# USB7206C.net
KiCad netlist of a schematic drawn in Altium Designer
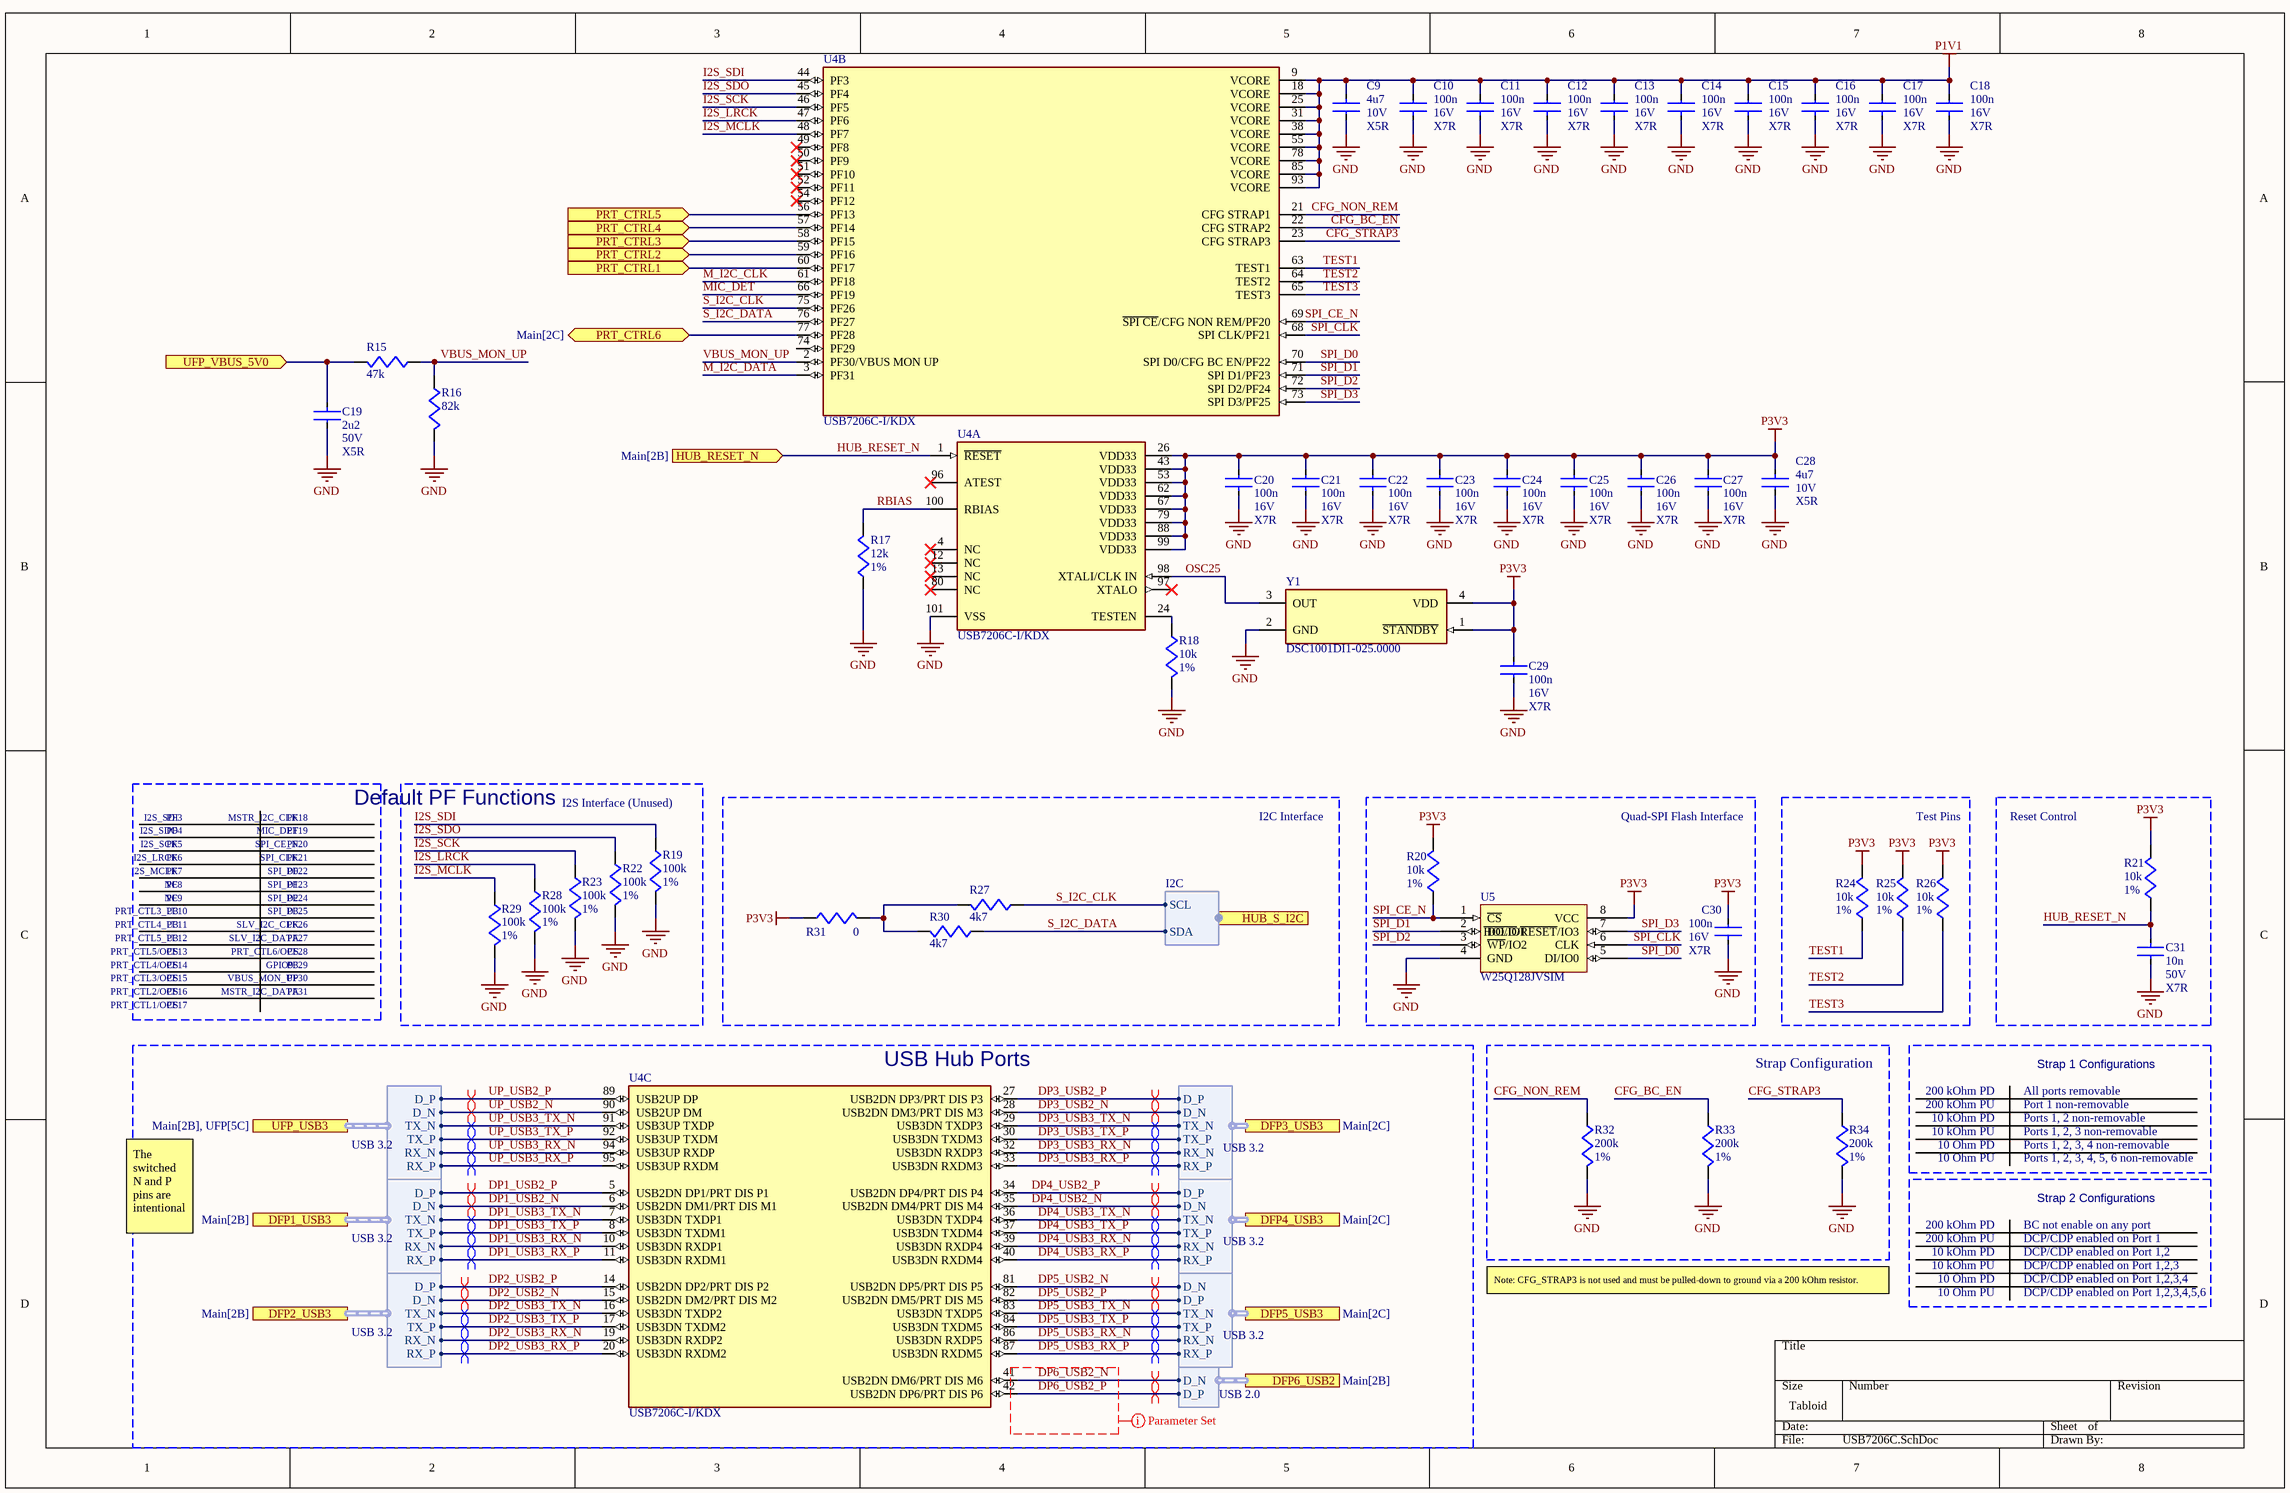
[diagram p0: USB7206C.SchDoc]

(export (version "E")
  (design (tool "Eeschema 10.0.6"))
  (components
    (comp (ref "C9")
      (value "4u7")
      (footprint "CAPC1005X06N")
      (description "10V 4.7uF X5R ±10% 0402 Multilayer Ceramic Capacitors MLCC - SMD/SMT ROHS")
      (fields
        (field (name "VOLTAGE") "10V")
        (field (name "DIELECTRIC") "X5R")
        (field (name "LCSC PART #") "C368809")
        (field (name "Comment") "4.7uF 10V 0402")
      )
      (libsource (lib "CWRU Motorsports") (part "Capacitor"))
    )
    (comp (ref "C10")
      (value "100n")
      (footprint "CAPC1005X06N")
      (description "16V 100nF X7R ±10% 0402 Multilayer Ceramic Capacitors MLCC - SMD/SMT ROHS")
      (fields
        (field (name "VOLTAGE") "16V")
        (field (name "DIELECTRIC") "X7R")
        (field (name "LCSC PART #") "C1525")
        (field (name "Comment") "100nF 16V 0402")
      )
      (libsource (lib "CWRU Motorsports") (part "Capacitor"))
    )
    (comp (ref "C11")
      (value "100n")
      (footprint "CAPC1005X06N")
      (description "16V 100nF X7R ±10% 0402 Multilayer Ceramic Capacitors MLCC - SMD/SMT ROHS")
      (fields
        (field (name "VOLTAGE") "16V")
        (field (name "DIELECTRIC") "X7R")
        (field (name "LCSC PART #") "C1525")
        (field (name "Comment") "100nF 16V 0402")
      )
      (libsource (lib "CWRU Motorsports") (part "Capacitor"))
    )
    (comp (ref "C12")
      (value "100n")
      (footprint "CAPC1005X06N")
      (description "16V 100nF X7R ±10% 0402 Multilayer Ceramic Capacitors MLCC - SMD/SMT ROHS")
      (fields
        (field (name "VOLTAGE") "16V")
        (field (name "DIELECTRIC") "X7R")
        (field (name "LCSC PART #") "C1525")
        (field (name "Comment") "100nF 16V 0402")
      )
      (libsource (lib "CWRU Motorsports") (part "Capacitor"))
    )
    (comp (ref "C13")
      (value "100n")
      (footprint "CAPC1005X06N")
      (description "16V 100nF X7R ±10% 0402 Multilayer Ceramic Capacitors MLCC - SMD/SMT ROHS")
      (fields
        (field (name "VOLTAGE") "16V")
        (field (name "DIELECTRIC") "X7R")
        (field (name "LCSC PART #") "C1525")
        (field (name "Comment") "100nF 16V 0402")
      )
      (libsource (lib "CWRU Motorsports") (part "Capacitor"))
    )
    (comp (ref "C14")
      (value "100n")
      (footprint "CAPC1005X06N")
      (description "16V 100nF X7R ±10% 0402 Multilayer Ceramic Capacitors MLCC - SMD/SMT ROHS")
      (fields
        (field (name "VOLTAGE") "16V")
        (field (name "DIELECTRIC") "X7R")
        (field (name "LCSC PART #") "C1525")
        (field (name "Comment") "100nF 16V 0402")
      )
      (libsource (lib "CWRU Motorsports") (part "Capacitor"))
    )
    (comp (ref "C15")
      (value "100n")
      (footprint "CAPC1005X06N")
      (description "16V 100nF X7R ±10% 0402 Multilayer Ceramic Capacitors MLCC - SMD/SMT ROHS")
      (fields
        (field (name "VOLTAGE") "16V")
        (field (name "DIELECTRIC") "X7R")
        (field (name "LCSC PART #") "C1525")
        (field (name "Comment") "100nF 16V 0402")
      )
      (libsource (lib "CWRU Motorsports") (part "Capacitor"))
    )
    (comp (ref "C16")
      (value "100n")
      (footprint "CAPC1005X06N")
      (description "16V 100nF X7R ±10% 0402 Multilayer Ceramic Capacitors MLCC - SMD/SMT ROHS")
      (fields
        (field (name "VOLTAGE") "16V")
        (field (name "DIELECTRIC") "X7R")
        (field (name "LCSC PART #") "C1525")
        (field (name "Comment") "100nF 16V 0402")
      )
      (libsource (lib "CWRU Motorsports") (part "Capacitor"))
    )
    (comp (ref "C17")
      (value "100n")
      (footprint "CAPC1005X06N")
      (description "16V 100nF X7R ±10% 0402 Multilayer Ceramic Capacitors MLCC - SMD/SMT ROHS")
      (fields
        (field (name "VOLTAGE") "16V")
        (field (name "DIELECTRIC") "X7R")
        (field (name "LCSC PART #") "C1525")
        (field (name "Comment") "100nF 16V 0402")
      )
      (libsource (lib "CWRU Motorsports") (part "Capacitor"))
    )
    (comp (ref "C18")
      (value "100n")
      (footprint "CAPC1005X06N")
      (description "16V 100nF X7R ±10% 0402 Multilayer Ceramic Capacitors MLCC - SMD/SMT ROHS")
      (fields
        (field (name "VOLTAGE") "16V")
        (field (name "DIELECTRIC") "X7R")
        (field (name "LCSC PART #") "C1525")
        (field (name "Comment") "100nF 16V 0402")
      )
      (libsource (lib "CWRU Motorsports") (part "Capacitor"))
    )
    (comp (ref "C19")
      (value "2u2")
      (footprint "CAPC2012X14N")
      (description "50V 2.2uF X5R ±10% 0805 Multilayer Ceramic Capacitors MLCC - SMD/SMT ROHS")
      (fields
        (field (name "VOLTAGE") "50V")
        (field (name "DIELECTRIC") "X5R")
        (field (name "LCSC PART #") "C377773")
        (field (name "Comment") "2.2uF 50V 0805")
      )
      (libsource (lib "CWRU Motorsports") (part "Capacitor"))
    )
    (comp (ref "C20")
      (value "100n")
      (footprint "CAPC1005X06N")
      (description "16V 100nF X7R ±10% 0402 Multilayer Ceramic Capacitors MLCC - SMD/SMT ROHS")
      (fields
        (field (name "VOLTAGE") "16V")
        (field (name "DIELECTRIC") "X7R")
        (field (name "LCSC PART #") "C1525")
        (field (name "Comment") "100nF 16V 0402")
      )
      (libsource (lib "CWRU Motorsports") (part "Capacitor"))
    )
    (comp (ref "C21")
      (value "100n")
      (footprint "CAPC1005X06N")
      (description "16V 100nF X7R ±10% 0402 Multilayer Ceramic Capacitors MLCC - SMD/SMT ROHS")
      (fields
        (field (name "VOLTAGE") "16V")
        (field (name "DIELECTRIC") "X7R")
        (field (name "LCSC PART #") "C1525")
        (field (name "Comment") "100nF 16V 0402")
      )
      (libsource (lib "CWRU Motorsports") (part "Capacitor"))
    )
    (comp (ref "C22")
      (value "100n")
      (footprint "CAPC1005X06N")
      (description "16V 100nF X7R ±10% 0402 Multilayer Ceramic Capacitors MLCC - SMD/SMT ROHS")
      (fields
        (field (name "VOLTAGE") "16V")
        (field (name "DIELECTRIC") "X7R")
        (field (name "LCSC PART #") "C1525")
        (field (name "Comment") "100nF 16V 0402")
      )
      (libsource (lib "CWRU Motorsports") (part "Capacitor"))
    )
    (comp (ref "C23")
      (value "100n")
      (footprint "CAPC1005X06N")
      (description "16V 100nF X7R ±10% 0402 Multilayer Ceramic Capacitors MLCC - SMD/SMT ROHS")
      (fields
        (field (name "VOLTAGE") "16V")
        (field (name "DIELECTRIC") "X7R")
        (field (name "LCSC PART #") "C1525")
        (field (name "Comment") "100nF 16V 0402")
      )
      (libsource (lib "CWRU Motorsports") (part "Capacitor"))
    )
    (comp (ref "C24")
      (value "100n")
      (footprint "CAPC1005X06N")
      (description "16V 100nF X7R ±10% 0402 Multilayer Ceramic Capacitors MLCC - SMD/SMT ROHS")
      (fields
        (field (name "VOLTAGE") "16V")
        (field (name "DIELECTRIC") "X7R")
        (field (name "LCSC PART #") "C1525")
        (field (name "Comment") "100nF 16V 0402")
      )
      (libsource (lib "CWRU Motorsports") (part "Capacitor"))
    )
    (comp (ref "C25")
      (value "100n")
      (footprint "CAPC1005X06N")
      (description "16V 100nF X7R ±10% 0402 Multilayer Ceramic Capacitors MLCC - SMD/SMT ROHS")
      (fields
        (field (name "VOLTAGE") "16V")
        (field (name "DIELECTRIC") "X7R")
        (field (name "LCSC PART #") "C1525")
        (field (name "Comment") "100nF 16V 0402")
      )
      (libsource (lib "CWRU Motorsports") (part "Capacitor"))
    )
    (comp (ref "C26")
      (value "100n")
      (footprint "CAPC1005X06N")
      (description "16V 100nF X7R ±10% 0402 Multilayer Ceramic Capacitors MLCC - SMD/SMT ROHS")
      (fields
        (field (name "VOLTAGE") "16V")
        (field (name "DIELECTRIC") "X7R")
        (field (name "LCSC PART #") "C1525")
        (field (name "Comment") "100nF 16V 0402")
      )
      (libsource (lib "CWRU Motorsports") (part "Capacitor"))
    )
    (comp (ref "C27")
      (value "100n")
      (footprint "CAPC1005X06N")
      (description "16V 100nF X7R ±10% 0402 Multilayer Ceramic Capacitors MLCC - SMD/SMT ROHS")
      (fields
        (field (name "VOLTAGE") "16V")
        (field (name "DIELECTRIC") "X7R")
        (field (name "LCSC PART #") "C1525")
        (field (name "Comment") "100nF 16V 0402")
      )
      (libsource (lib "CWRU Motorsports") (part "Capacitor"))
    )
    (comp (ref "C28")
      (value "4u7")
      (footprint "CAPC1005X06N")
      (description "10V 4.7uF X5R ±10% 0402 Multilayer Ceramic Capacitors MLCC - SMD/SMT ROHS")
      (fields
        (field (name "VOLTAGE") "10V")
        (field (name "DIELECTRIC") "X5R")
        (field (name "LCSC PART #") "C368809")
        (field (name "Comment") "4.7uF 10V 0402")
      )
      (libsource (lib "CWRU Motorsports") (part "Capacitor"))
    )
    (comp (ref "C29")
      (value "100n")
      (footprint "CAPC1005X06N")
      (description "16V 100nF X7R ±10% 0402 Multilayer Ceramic Capacitors MLCC - SMD/SMT ROHS")
      (fields
        (field (name "VOLTAGE") "16V")
        (field (name "DIELECTRIC") "X7R")
        (field (name "LCSC PART #") "C1525")
        (field (name "Comment") "100nF 16V 0402")
      )
      (libsource (lib "CWRU Motorsports") (part "Capacitor"))
    )
    (comp (ref "C30")
      (value "100n")
      (footprint "CAPC1005X06N")
      (description "16V 100nF X7R ±10% 0402 Multilayer Ceramic Capacitors MLCC - SMD/SMT ROHS")
      (fields
        (field (name "VOLTAGE") "16V")
        (field (name "DIELECTRIC") "X7R")
        (field (name "LCSC PART #") "C1525")
        (field (name "Comment") "100nF 16V 0402")
      )
      (libsource (lib "CWRU Motorsports") (part "Capacitor"))
    )
    (comp (ref "C31")
      (value "10n")
      (footprint "CAPC1005X06N")
      (description "50V 10nF X7R ±10% 0402 Multilayer Ceramic Capacitors MLCC - SMD/SMT ROHS")
      (fields
        (field (name "VOLTAGE") "50V")
        (field (name "DIELECTRIC") "X7R")
        (field (name "LCSC PART #") "C60133")
        (field (name "Comment") "10n 50V X7R 0402")
      )
      (libsource (lib "CWRU Motorsports") (part "Capacitor"))
    )
    (comp (ref "R15")
      (value "47k")
      (footprint "RESC1005X04M")
      (description "62.5mW Thick Film Resistors 50V ±100ppm/℃ ±5% 47kΩ 0402 Chip Resistor - Surface Mount ROHS")
      (fields (field (name "TOLERANCE") "1%") (field (name "LCSC PART #") "C163440"))
      (libsource (lib "CWRU Motorsports") (part "Resistor"))
    )
    (comp (ref "R16")
      (value "82k")
      (footprint "RESC1005X04M")
      (description "62.5mW Thick Film Resistors 50V ±100ppm/℃ ±1% 82kΩ 0402 Chip Resistor - Surface Mount ROHS")
      (fields (field (name "TOLERANCE") "1%") (field (name "LCSC PART #") "C137932"))
      (libsource (lib "CWRU Motorsports") (part "Resistor"))
    )
    (comp (ref "R17")
      (value "12k")
      (footprint "RESC1005X04M")
      (description "62.5mW Thick Film Resistors 50V ±100ppm/℃ ±1% 12kΩ 0402 Chip Resistor - Surface Mount ROHS")
      (fields
        (field (name "TOLERANCE") "1%")
        (field (name "LCSC PART #") "C114760")
        (field (name "Comment") "12k 1% 0402")
      )
      (libsource (lib "CWRU Motorsports") (part "Resistor"))
    )
    (comp (ref "R18")
      (value "10k")
      (footprint "RESC1005X04M")
      (description "62.5mW Thick Film Resistors 50V ±100ppm/℃ ±1% 10kΩ 0402 Chip Resistor - Surface Mount ROHS")
      (fields
        (field (name "TOLERANCE") "1%")
        (field (name "LCSC PART #") "C60490")
        (field (name "Comment") "10k 1% 0402")
      )
      (libsource (lib "CWRU Motorsports") (part "Resistor"))
    )
    (comp (ref "R19")
      (value "100k")
      (footprint "RESC1005X04M")
      (description "62.5mW Thick Film Resistors 50V ±100ppm/℃ ±1% 100kΩ 0402 Chip Resistor - Surface Mount ROHS")
      (fields
        (field (name "TOLERANCE") "1%")
        (field (name "LCSC PART #") "C60491")
        (field (name "Comment") "100k 1% 0402")
      )
      (libsource (lib "CWRU Motorsports") (part "Resistor"))
    )
    (comp (ref "R20")
      (value "10k")
      (footprint "RESC1005X04M")
      (description "62.5mW Thick Film Resistors 50V ±100ppm/℃ ±1% 10kΩ 0402 Chip Resistor - Surface Mount ROHS")
      (fields
        (field (name "TOLERANCE") "1%")
        (field (name "LCSC PART #") "C60490")
        (field (name "Comment") "10k 1% 0402")
      )
      (libsource (lib "CWRU Motorsports") (part "Resistor"))
    )
    (comp (ref "R21")
      (value "10k")
      (footprint "RESC1005X04M")
      (description "62.5mW Thick Film Resistors 50V ±100ppm/℃ ±1% 10kΩ 0402 Chip Resistor - Surface Mount ROHS")
      (fields
        (field (name "TOLERANCE") "1%")
        (field (name "LCSC PART #") "C60490")
        (field (name "Comment") "10k 1% 0402")
      )
      (libsource (lib "CWRU Motorsports") (part "Resistor"))
    )
    (comp (ref "R22")
      (value "100k")
      (footprint "RESC1005X04M")
      (description "62.5mW Thick Film Resistors 50V ±100ppm/℃ ±1% 100kΩ 0402 Chip Resistor - Surface Mount ROHS")
      (fields
        (field (name "TOLERANCE") "1%")
        (field (name "LCSC PART #") "C60491")
        (field (name "Comment") "100k 1% 0402")
      )
      (libsource (lib "CWRU Motorsports") (part "Resistor"))
    )
    (comp (ref "R23")
      (value "100k")
      (footprint "RESC1005X04M")
      (description "62.5mW Thick Film Resistors 50V ±100ppm/℃ ±1% 100kΩ 0402 Chip Resistor - Surface Mount ROHS")
      (fields
        (field (name "TOLERANCE") "1%")
        (field (name "LCSC PART #") "C60491")
        (field (name "Comment") "100k 1% 0402")
      )
      (libsource (lib "CWRU Motorsports") (part "Resistor"))
    )
    (comp (ref "R24")
      (value "10k")
      (footprint "RESC1005X04M")
      (description "62.5mW Thick Film Resistors 50V ±100ppm/℃ ±1% 10kΩ 0402 Chip Resistor - Surface Mount ROHS")
      (fields
        (field (name "TOLERANCE") "1%")
        (field (name "LCSC PART #") "C60490")
        (field (name "Comment") "10k 1% 0402")
      )
      (libsource (lib "CWRU Motorsports") (part "Resistor"))
    )
    (comp (ref "R25")
      (value "10k")
      (footprint "RESC1005X04M")
      (description "62.5mW Thick Film Resistors 50V ±100ppm/℃ ±1% 10kΩ 0402 Chip Resistor - Surface Mount ROHS")
      (fields
        (field (name "TOLERANCE") "1%")
        (field (name "LCSC PART #") "C60490")
        (field (name "Comment") "10k 1% 0402")
      )
      (libsource (lib "CWRU Motorsports") (part "Resistor"))
    )
    (comp (ref "R26")
      (value "10k")
      (footprint "RESC1005X04M")
      (description "62.5mW Thick Film Resistors 50V ±100ppm/℃ ±1% 10kΩ 0402 Chip Resistor - Surface Mount ROHS")
      (fields
        (field (name "TOLERANCE") "1%")
        (field (name "LCSC PART #") "C60490")
        (field (name "Comment") "10k 1% 0402")
      )
      (libsource (lib "CWRU Motorsports") (part "Resistor"))
    )
    (comp (ref "R27")
      (value "4k7")
      (footprint "RESC1005X04M")
      (description "62.5mW Thick Film Resistors 50V ±100ppm/℃ ±5% 4.7kΩ 0402 Chip Resistor - Surface Mount ROHS")
      (fields (field (name "TOLERANCE") "5%") (field (name "LCSC PART #") "C105870"))
      (libsource (lib "CWRU Motorsports") (part "Resistor"))
    )
    (comp (ref "R28")
      (value "100k")
      (footprint "RESC1005X04M")
      (description "62.5mW Thick Film Resistors 50V ±100ppm/℃ ±1% 100kΩ 0402 Chip Resistor - Surface Mount ROHS")
      (fields
        (field (name "TOLERANCE") "1%")
        (field (name "LCSC PART #") "C60491")
        (field (name "Comment") "100k 1% 0402")
      )
      (libsource (lib "CWRU Motorsports") (part "Resistor"))
    )
    (comp (ref "R29")
      (value "100k")
      (footprint "RESC1005X04M")
      (description "62.5mW Thick Film Resistors 50V ±100ppm/℃ ±1% 100kΩ 0402 Chip Resistor - Surface Mount ROHS")
      (fields
        (field (name "TOLERANCE") "1%")
        (field (name "LCSC PART #") "C60491")
        (field (name "Comment") "100k 1% 0402")
      )
      (libsource (lib "CWRU Motorsports") (part "Resistor"))
    )
    (comp (ref "R30")
      (value "4k7")
      (footprint "RESC1005X04M")
      (description "62.5mW Thick Film Resistors 50V ±100ppm/℃ ±5% 4.7kΩ 0402 Chip Resistor - Surface Mount ROHS")
      (fields (field (name "TOLERANCE") "5%") (field (name "LCSC PART #") "C105870"))
      (libsource (lib "CWRU Motorsports") (part "Resistor"))
    )
    (comp (ref "R31")
      (value "0")
      (footprint "RESC1508X05M")
      (description "62.5mW Thick Film Resistors 50V 0Ω 0402 Chip Resistor - Surface Mount ROHS")
      (fields (field (name "TOLERANCE") "1%") (field (name "LCSC PART #") "C60485"))
      (libsource (lib "CWRU Motorsports") (part "Resistor"))
    )
    (comp (ref "R32")
      (value "200k")
      (footprint "RESC1005X04M")
      (description "62.5mW Thick Film Resistors 50V ±100ppm/℃ ±1% 200kΩ 0402 Chip Resistor - Surface Mount ROHS")
      (fields
        (field (name "TOLERANCE") "1%")
        (field (name "LCSC PART #") "C114763")
        (field (name "Comment") "200k 1% 0402")
      )
      (libsource (lib "CWRU Motorsports") (part "Resistor"))
    )
    (comp (ref "R33")
      (value "200k")
      (footprint "RESC1005X04M")
      (description "62.5mW Thick Film Resistors 50V ±100ppm/℃ ±1% 200kΩ 0402 Chip Resistor - Surface Mount ROHS")
      (fields
        (field (name "TOLERANCE") "1%")
        (field (name "LCSC PART #") "C114763")
        (field (name "Comment") "200k 1% 0402")
      )
      (libsource (lib "CWRU Motorsports") (part "Resistor"))
    )
    (comp (ref "R34")
      (value "200k")
      (footprint "RESC1005X04M")
      (description "62.5mW Thick Film Resistors 50V ±100ppm/℃ ±1% 200kΩ 0402 Chip Resistor - Surface Mount ROHS")
      (fields
        (field (name "TOLERANCE") "1%")
        (field (name "LCSC PART #") "C114763")
        (field (name "Comment") "200k 1% 0402")
      )
      (libsource (lib "CWRU Motorsports") (part "Resistor"))
    )
    (comp (ref "U4")
      (value "USB7206C-I/KDX")
      (footprint "FP-C04-407-IPC_A")
      (description "USB3.1 GEN2 Hub_no Pd_no Type C 100 VQFN 12X12X0.9MM Tray Rohs Compliant: Yes")
      (libsource (lib "CWRU Motorsports") (part "e6d06bc286127564edabf54f428b06f"))
    )
    (comp (ref "U5")
      (value "W25Q128JVSIM")
      (footprint "SOIC127P790X216-8N")
      (description "NOR Flash Serial (SPI, Dual SPI, Quad SPI) 3V/3.3V 128M-bit 16M x 8 6ns 8-Pin SOIC Tube")
      (libsource (lib "CWRU Motorsports") (part "W25Q128JVSIM-Symbol-1"))
    )
    (comp (ref "Y1")
      (value "DSC1001DI1-025.0000")
      (footprint "FP-CDFN2520-4LD-PL-1-MFG")
      (description "MEMS OSC XO 25.0000MHZ CMOS SMD")
      (libsource (lib "Altium Content Vault") (part "8720c5899389794f50cb41edc4e4c8a"))
    )
  )
  (nets
    (net (code "7") (name "/CFG_BC_EN") (class "Default")
      (node (ref "R33") (pin "1") (pinfunction "1_1") (pintype "passive"))
      (node (ref "U4") (pin "22") (pinfunction "CFG_STRAP2_22") (pintype "passive"))
    )
    (net (code "8") (name "/CFG_NON_REM") (class "Default")
      (node (ref "R32") (pin "1") (pinfunction "1_1") (pintype "passive"))
      (node (ref "U4") (pin "21") (pinfunction "CFG_STRAP1_21") (pintype "passive"))
    )
    (net (code "9") (name "/CFG_STRAP3") (class "Default")
      (node (ref "R34") (pin "1") (pinfunction "1_1") (pintype "passive"))
      (node (ref "U4") (pin "23") (pinfunction "CFG_STRAP3_23") (pintype "passive"))
    )
    (net (code "10") (name "/DP1_USB2_N") (class "Default")
      (node (ref "U4") (pin "6") (pinfunction "USB2DN_DM1/PRT_DIS_M1_6") (pintype "bidirectional"))
    )
    (net (code "11") (name "/DP1_USB2_P") (class "Default")
      (node (ref "U4") (pin "5") (pinfunction "USB2DN_DP1/PRT_DIS_P1_5") (pintype "bidirectional"))
    )
    (net (code "12") (name "/DP1_USB3_RX_N") (class "Default")
      (node (ref "U4") (pin "10") (pinfunction "USB3DN_RXDP1_10") (pintype "bidirectional"))
    )
    (net (code "13") (name "/DP1_USB3_RX_P") (class "Default")
      (node (ref "U4") (pin "11") (pinfunction "USB3DN_RXDM1_11") (pintype "bidirectional"))
    )
    (net (code "14") (name "/DP1_USB3_TX_N") (class "Default")
      (node (ref "U4") (pin "7") (pinfunction "USB3DN_TXDP1_7") (pintype "bidirectional"))
    )
    (net (code "15") (name "/DP1_USB3_TX_P") (class "Default")
      (node (ref "U4") (pin "8") (pinfunction "USB3DN_TXDM1_8") (pintype "bidirectional"))
    )
    (net (code "16") (name "/DP2_USB2_N") (class "Default")
      (node (ref "U4") (pin "15") (pinfunction "USB2DN_DM2/PRT_DIS_M2_15") (pintype "bidirectional"))
    )
    (net (code "17") (name "/DP2_USB2_P") (class "Default")
      (node (ref "U4") (pin "14") (pinfunction "USB2DN_DP2/PRT_DIS_P2_14") (pintype "bidirectional"))
    )
    (net (code "18") (name "/DP2_USB3_RX_N") (class "Default")
      (node (ref "U4") (pin "19") (pinfunction "USB3DN_RXDP2_19") (pintype "bidirectional"))
    )
    (net (code "19") (name "/DP2_USB3_RX_P") (class "Default")
      (node (ref "U4") (pin "20") (pinfunction "USB3DN_RXDM2_20") (pintype "bidirectional"))
    )
    (net (code "20") (name "/DP2_USB3_TX_N") (class "Default")
      (node (ref "U4") (pin "16") (pinfunction "USB3DN_TXDP2_16") (pintype "bidirectional"))
    )
    (net (code "21") (name "/DP2_USB3_TX_P") (class "Default")
      (node (ref "U4") (pin "17") (pinfunction "USB3DN_TXDM2_17") (pintype "bidirectional"))
    )
    (net (code "22") (name "/DP3_USB2_N") (class "Default")
      (node (ref "U4") (pin "28") (pinfunction "USB2DN_DM3/PRT_DIS_M3_28") (pintype "bidirectional"))
    )
    (net (code "23") (name "/DP3_USB2_P") (class "Default")
      (node (ref "U4") (pin "27") (pinfunction "USB2DN_DP3/PRT_DIS_P3_27") (pintype "bidirectional"))
    )
    (net (code "24") (name "/DP3_USB3_RX_N") (class "Default")
      (node (ref "U4") (pin "32") (pinfunction "USB3DN_RXDP3_32") (pintype "bidirectional"))
    )
    (net (code "25") (name "/DP3_USB3_RX_P") (class "Default")
      (node (ref "U4") (pin "33") (pinfunction "USB3DN_RXDM3_33") (pintype "bidirectional"))
    )
    (net (code "26") (name "/DP3_USB3_TX_N") (class "Default")
      (node (ref "U4") (pin "29") (pinfunction "USB3DN_TXDP3_29") (pintype "bidirectional"))
    )
    (net (code "27") (name "/DP3_USB3_TX_P") (class "Default")
      (node (ref "U4") (pin "30") (pinfunction "USB3DN_TXDM3_30") (pintype "bidirectional"))
    )
    (net (code "28") (name "/DP4_USB2_N") (class "Default")
      (node (ref "U4") (pin "35") (pinfunction "USB2DN_DM4/PRT_DIS_M4_35") (pintype "bidirectional"))
    )
    (net (code "29") (name "/DP4_USB2_P") (class "Default")
      (node (ref "U4") (pin "34") (pinfunction "USB2DN_DP4/PRT_DIS_P4_34") (pintype "bidirectional"))
    )
    (net (code "30") (name "/DP4_USB3_RX_N") (class "Default")
      (node (ref "U4") (pin "39") (pinfunction "USB3DN_RXDP4_39") (pintype "bidirectional"))
    )
    (net (code "31") (name "/DP4_USB3_RX_P") (class "Default")
      (node (ref "U4") (pin "40") (pinfunction "USB3DN_RXDM4_40") (pintype "bidirectional"))
    )
    (net (code "32") (name "/DP4_USB3_TX_N") (class "Default")
      (node (ref "U4") (pin "36") (pinfunction "USB3DN_TXDP4_36") (pintype "bidirectional"))
    )
    (net (code "33") (name "/DP4_USB3_TX_P") (class "Default")
      (node (ref "U4") (pin "37") (pinfunction "USB3DN_TXDM4_37") (pintype "bidirectional"))
    )
    (net (code "34") (name "/DP5_USB2_N") (class "Default")
      (node (ref "U4") (pin "81") (pinfunction "USB2DN_DP5/PRT_DIS_P5_81") (pintype "bidirectional"))
    )
    (net (code "35") (name "/DP5_USB2_P") (class "Default")
      (node (ref "U4") (pin "82") (pinfunction "USB2DN_DM5/PRT_DIS_M5_82") (pintype "bidirectional"))
    )
    (net (code "36") (name "/DP5_USB3_RX_N") (class "Default")
      (node (ref "U4") (pin "86") (pinfunction "USB3DN_RXDP5_86") (pintype "bidirectional"))
    )
    (net (code "37") (name "/DP5_USB3_RX_P") (class "Default")
      (node (ref "U4") (pin "87") (pinfunction "USB3DN_RXDM5_87") (pintype "bidirectional"))
    )
    (net (code "38") (name "/DP5_USB3_TX_N") (class "Default")
      (node (ref "U4") (pin "83") (pinfunction "USB3DN_TXDP5_83") (pintype "bidirectional"))
    )
    (net (code "39") (name "/DP5_USB3_TX_P") (class "Default")
      (node (ref "U4") (pin "84") (pinfunction "USB3DN_TXDM5_84") (pintype "bidirectional"))
    )
    (net (code "40") (name "/DP6_USB2_N") (class "Default")
      (node (ref "U4") (pin "41") (pinfunction "USB2DN_DM6/PRT_DIS_M6_41") (pintype "bidirectional"))
    )
    (net (code "41") (name "/DP6_USB2_P") (class "Default")
      (node (ref "U4") (pin "42") (pinfunction "USB2DN_DP6/PRT_DIS_P6_42") (pintype "bidirectional"))
    )
    (net (code "42") (name "/HUB_RESET_N") (class "Default")
      (node (ref "C31") (pin "1") (pinfunction "1_1") (pintype "passive"))
      (node (ref "R21") (pin "1") (pinfunction "1_1") (pintype "passive"))
      (node (ref "U4") (pin "1") (pinfunction "~{RESET}_1") (pintype "input"))
    )
    (net (code "43") (name "/I2S_LRCK") (class "Default")
      (node (ref "R28") (pin "1") (pinfunction "1_1") (pintype "passive"))
      (node (ref "U4") (pin "47") (pinfunction "PF6_47") (pintype "bidirectional"))
    )
    (net (code "44") (name "/I2S_MCLK") (class "Default")
      (node (ref "R29") (pin "1") (pinfunction "1_1") (pintype "passive"))
      (node (ref "U4") (pin "48") (pinfunction "PF7_48") (pintype "bidirectional"))
    )
    (net (code "45") (name "/I2S_SCK") (class "Default")
      (node (ref "R23") (pin "1") (pinfunction "1_1") (pintype "passive"))
      (node (ref "U4") (pin "46") (pinfunction "PF5_46") (pintype "bidirectional"))
    )
    (net (code "46") (name "/I2S_SDI") (class "Default")
      (node (ref "R19") (pin "1") (pinfunction "1_1") (pintype "passive"))
      (node (ref "U4") (pin "44") (pinfunction "PF3_44") (pintype "bidirectional"))
    )
    (net (code "47") (name "/I2S_SDO") (class "Default")
      (node (ref "R22") (pin "1") (pinfunction "1_1") (pintype "passive"))
      (node (ref "U4") (pin "45") (pinfunction "PF4_45") (pintype "bidirectional"))
    )
    (net (code "48") (name "/MIC_DET") (class "Default")
      (node (ref "U4") (pin "66") (pinfunction "PF19_66") (pintype "bidirectional"))
    )
    (net (code "49") (name "/M_I2C_CLK") (class "Default")
      (node (ref "U4") (pin "61") (pinfunction "PF18_61") (pintype "bidirectional"))
    )
    (net (code "50") (name "/M_I2C_DATA") (class "Default")
      (node (ref "U4") (pin "3") (pinfunction "PF31_3") (pintype "bidirectional"))
    )
    (net (code "51") (name "/OSC25") (class "Default")
      (node (ref "U4") (pin "98") (pinfunction "XTALI/CLK_IN_98") (pintype "input"))
      (node (ref "Y1") (pin "3") (pinfunction "OUT_3") (pintype "passive"))
    )
    (net (code "52") (name "/PRT_CTRL1") (class "Default")
      (node (ref "U4") (pin "60") (pinfunction "PF17_60") (pintype "bidirectional"))
    )
    (net (code "53") (name "/PRT_CTRL2") (class "Default")
      (node (ref "U4") (pin "59") (pinfunction "PF16_59") (pintype "bidirectional"))
    )
    (net (code "54") (name "/PRT_CTRL3") (class "Default")
      (node (ref "U4") (pin "58") (pinfunction "PF15_58") (pintype "bidirectional"))
    )
    (net (code "55") (name "/PRT_CTRL4") (class "Default")
      (node (ref "U4") (pin "57") (pinfunction "PF14_57") (pintype "bidirectional"))
    )
    (net (code "56") (name "/PRT_CTRL5") (class "Default")
      (node (ref "U4") (pin "56") (pinfunction "PF13_56") (pintype "bidirectional"))
    )
    (net (code "57") (name "/PRT_CTRL6") (class "Default")
      (node (ref "U4") (pin "77") (pinfunction "PF28_77") (pintype "bidirectional"))
    )
    (net (code "58") (name "/RBIAS") (class "Default")
      (node (ref "R17") (pin "1") (pinfunction "1_1") (pintype "passive"))
      (node (ref "U4") (pin "100") (pinfunction "RBIAS_100") (pintype "passive"))
    )
    (net (code "59") (name "/SPI_CE_N") (class "Default")
      (node (ref "R20") (pin "1") (pinfunction "1_1") (pintype "passive"))
      (node (ref "U4") (pin "69") (pinfunction "~{SPI_CE}/CFG_NON_REM/PF20_69") (pintype "input"))
      (node (ref "U5") (pin "1") (pinfunction "~{CS}_1") (pintype "input"))
    )
    (net (code "60") (name "/SPI_CLK") (class "Default")
      (node (ref "U4") (pin "68") (pinfunction "SPI_CLK/PF21_68") (pintype "input"))
      (node (ref "U5") (pin "6") (pinfunction "CLK_6") (pintype "input"))
    )
    (net (code "61") (name "/SPI_D0") (class "Default")
      (node (ref "U4") (pin "70") (pinfunction "SPI_D0/CFG_BC_EN/PF22_70") (pintype "input"))
      (node (ref "U5") (pin "5") (pinfunction "DI/IO0_5") (pintype "bidirectional"))
    )
    (net (code "62") (name "/SPI_D1") (class "Default")
      (node (ref "U4") (pin "71") (pinfunction "SPI_D1/PF23_71") (pintype "input"))
      (node (ref "U5") (pin "2") (pinfunction "DO/IO1_2") (pintype "bidirectional"))
    )
    (net (code "63") (name "/SPI_D2") (class "Default")
      (node (ref "U4") (pin "72") (pinfunction "SPI_D2/PF24_72") (pintype "input"))
      (node (ref "U5") (pin "3") (pinfunction "~{WP}/IO2_3") (pintype "bidirectional"))
    )
    (net (code "64") (name "/SPI_D3") (class "Default")
      (node (ref "U4") (pin "73") (pinfunction "SPI_D3/PF25_73") (pintype "input"))
      (node (ref "U5") (pin "7") (pinfunction "~{HOLD}/~{RESET}/IO3_7") (pintype "bidirectional"))
    )
    (net (code "65") (name "/S_I2C_CLK") (class "Default")
      (node (ref "R27") (pin "1") (pinfunction "1_1") (pintype "passive"))
      (node (ref "U4") (pin "75") (pinfunction "PF26_75") (pintype "bidirectional"))
    )
    (net (code "66") (name "/S_I2C_DATA") (class "Default")
      (node (ref "R30") (pin "1") (pinfunction "1_1") (pintype "passive"))
      (node (ref "U4") (pin "76") (pinfunction "PF27_76") (pintype "bidirectional"))
    )
    (net (code "67") (name "/TEST1") (class "Default")
      (node (ref "R24") (pin "1") (pinfunction "1_1") (pintype "passive"))
      (node (ref "U4") (pin "63") (pinfunction "TEST1_63") (pintype "passive"))
    )
    (net (code "68") (name "/TEST2") (class "Default")
      (node (ref "R25") (pin "1") (pinfunction "1_1") (pintype "passive"))
      (node (ref "U4") (pin "64") (pinfunction "TEST2_64") (pintype "passive"))
    )
    (net (code "69") (name "/TEST3") (class "Default")
      (node (ref "R26") (pin "1") (pinfunction "1_1") (pintype "passive"))
      (node (ref "U4") (pin "65") (pinfunction "TEST3_65") (pintype "passive"))
    )
    (net (code "71") (name "/UFP_VBUS_5V0") (class "Default")
      (node (ref "C19") (pin "1") (pinfunction "1_1") (pintype "passive"))
      (node (ref "R15") (pin "1") (pinfunction "1_1") (pintype "passive"))
    )
    (net (code "72") (name "/UP_USB2_N") (class "Default")
      (node (ref "U4") (pin "90") (pinfunction "USB2UP_DM_90") (pintype "bidirectional"))
    )
    (net (code "73") (name "/UP_USB2_P") (class "Default")
      (node (ref "U4") (pin "89") (pinfunction "USB2UP_DP_89") (pintype "bidirectional"))
    )
    (net (code "74") (name "/UP_USB3_RX_N") (class "Default")
      (node (ref "U4") (pin "94") (pinfunction "USB3UP_RXDP_94") (pintype "bidirectional"))
    )
    (net (code "75") (name "/UP_USB3_RX_P") (class "Default")
      (node (ref "U4") (pin "95") (pinfunction "USB3UP_RXDM_95") (pintype "bidirectional"))
    )
    (net (code "76") (name "/UP_USB3_TX_N") (class "Default")
      (node (ref "U4") (pin "91") (pinfunction "USB3UP_TXDP_91") (pintype "bidirectional"))
    )
    (net (code "77") (name "/UP_USB3_TX_P") (class "Default")
      (node (ref "U4") (pin "92") (pinfunction "USB3UP_TXDM_92") (pintype "bidirectional"))
    )
    (net (code "78") (name "/VBUS_MON_UP") (class "Default")
      (node (ref "R15") (pin "2") (pinfunction "2_2") (pintype "passive"))
      (node (ref "R16") (pin "2") (pinfunction "2_2") (pintype "passive"))
      (node (ref "U4") (pin "2") (pinfunction "PF30/VBUS_MON_UP_2") (pintype "bidirectional"))
    )
    (net (code "82") (name "GND") (class "Default")
      (node (ref "C10") (pin "1") (pinfunction "1_1") (pintype "passive"))
      (node (ref "C11") (pin "1") (pinfunction "1_1") (pintype "passive"))
      (node (ref "C12") (pin "1") (pinfunction "1_1") (pintype "passive"))
      (node (ref "C13") (pin "1") (pinfunction "1_1") (pintype "passive"))
      (node (ref "C14") (pin "1") (pinfunction "1_1") (pintype "passive"))
      (node (ref "C15") (pin "1") (pinfunction "1_1") (pintype "passive"))
      (node (ref "C16") (pin "1") (pinfunction "1_1") (pintype "passive"))
      (node (ref "C17") (pin "1") (pinfunction "1_1") (pintype "passive"))
      (node (ref "C18") (pin "1") (pinfunction "1_1") (pintype "passive"))
      (node (ref "C19") (pin "2") (pinfunction "2_2") (pintype "passive"))
      (node (ref "C20") (pin "1") (pinfunction "1_1") (pintype "passive"))
      (node (ref "C21") (pin "1") (pinfunction "1_1") (pintype "passive"))
      (node (ref "C22") (pin "1") (pinfunction "1_1") (pintype "passive"))
      (node (ref "C23") (pin "1") (pinfunction "1_1") (pintype "passive"))
      (node (ref "C24") (pin "1") (pinfunction "1_1") (pintype "passive"))
      (node (ref "C25") (pin "1") (pinfunction "1_1") (pintype "passive"))
      (node (ref "C26") (pin "1") (pinfunction "1_1") (pintype "passive"))
      (node (ref "C27") (pin "1") (pinfunction "1_1") (pintype "passive"))
      (node (ref "C28") (pin "2") (pinfunction "2_2") (pintype "passive"))
      (node (ref "C29") (pin "2") (pinfunction "2_2") (pintype "passive"))
      (node (ref "C30") (pin "1") (pinfunction "1_1") (pintype "passive"))
      (node (ref "C31") (pin "2") (pinfunction "2_2") (pintype "passive"))
      (node (ref "C9") (pin "2") (pinfunction "2_2") (pintype "passive"))
      (node (ref "R16") (pin "1") (pinfunction "1_1") (pintype "passive"))
      (node (ref "R17") (pin "2") (pinfunction "2_2") (pintype "passive"))
      (node (ref "R18") (pin "1") (pinfunction "1_1") (pintype "passive"))
      (node (ref "R19") (pin "2") (pinfunction "2_2") (pintype "passive"))
      (node (ref "R22") (pin "2") (pinfunction "2_2") (pintype "passive"))
      (node (ref "R23") (pin "2") (pinfunction "2_2") (pintype "passive"))
      (node (ref "R28") (pin "2") (pinfunction "2_2") (pintype "passive"))
      (node (ref "R29") (pin "2") (pinfunction "2_2") (pintype "passive"))
      (node (ref "R32") (pin "2") (pinfunction "2_2") (pintype "passive"))
      (node (ref "R33") (pin "2") (pinfunction "2_2") (pintype "passive"))
      (node (ref "R34") (pin "2") (pinfunction "2_2") (pintype "passive"))
      (node (ref "U4") (pin "101") (pinfunction "VSS_101") (pintype "power_in"))
      (node (ref "U5") (pin "4") (pinfunction "GND_4") (pintype "power_in"))
      (node (ref "Y1") (pin "2") (pinfunction "GND_2") (pintype "power_in"))
    )
    (net (code "83") (name "Net-(R27-Pad2)") (class "Default")
      (node (ref "R27") (pin "2") (pinfunction "2_2") (pintype "passive"))
      (node (ref "R30") (pin "2") (pinfunction "2_2") (pintype "passive"))
      (node (ref "R31") (pin "2") (pinfunction "2_2") (pintype "passive"))
    )
    (net (code "84") (name "Net-(U4A-TESTEN)") (class "Default")
      (node (ref "R18") (pin "2") (pinfunction "2_2") (pintype "passive"))
      (node (ref "U4") (pin "24") (pinfunction "TESTEN_24") (pintype "passive"))
    )
    (net (code "85") (name "P1V1") (class "Default")
      (node (ref "C10") (pin "2") (pinfunction "2_2") (pintype "passive"))
      (node (ref "C11") (pin "2") (pinfunction "2_2") (pintype "passive"))
      (node (ref "C12") (pin "2") (pinfunction "2_2") (pintype "passive"))
      (node (ref "C13") (pin "2") (pinfunction "2_2") (pintype "passive"))
      (node (ref "C14") (pin "2") (pinfunction "2_2") (pintype "passive"))
      (node (ref "C15") (pin "2") (pinfunction "2_2") (pintype "passive"))
      (node (ref "C16") (pin "2") (pinfunction "2_2") (pintype "passive"))
      (node (ref "C17") (pin "2") (pinfunction "2_2") (pintype "passive"))
      (node (ref "C18") (pin "2") (pinfunction "2_2") (pintype "passive"))
      (node (ref "C9") (pin "1") (pinfunction "1_1") (pintype "passive"))
      (node (ref "U4") (pin "18") (pinfunction "VCORE_18") (pintype "power_in"))
      (node (ref "U4") (pin "25") (pinfunction "VCORE_25") (pintype "power_in"))
      (node (ref "U4") (pin "31") (pinfunction "VCORE_31") (pintype "power_in"))
      (node (ref "U4") (pin "38") (pinfunction "VCORE_38") (pintype "power_in"))
      (node (ref "U4") (pin "55") (pinfunction "VCORE_55") (pintype "power_in"))
      (node (ref "U4") (pin "78") (pinfunction "VCORE_78") (pintype "power_in"))
      (node (ref "U4") (pin "85") (pinfunction "VCORE_85") (pintype "power_in"))
      (node (ref "U4") (pin "9") (pinfunction "VCORE_9") (pintype "power_in"))
      (node (ref "U4") (pin "93") (pinfunction "VCORE_93") (pintype "power_in"))
    )
    (net (code "86") (name "P3V3") (class "Default")
      (node (ref "C20") (pin "2") (pinfunction "2_2") (pintype "passive"))
      (node (ref "C21") (pin "2") (pinfunction "2_2") (pintype "passive"))
      (node (ref "C22") (pin "2") (pinfunction "2_2") (pintype "passive"))
      (node (ref "C23") (pin "2") (pinfunction "2_2") (pintype "passive"))
      (node (ref "C24") (pin "2") (pinfunction "2_2") (pintype "passive"))
      (node (ref "C25") (pin "2") (pinfunction "2_2") (pintype "passive"))
      (node (ref "C26") (pin "2") (pinfunction "2_2") (pintype "passive"))
      (node (ref "C27") (pin "2") (pinfunction "2_2") (pintype "passive"))
      (node (ref "C28") (pin "1") (pinfunction "1_1") (pintype "passive"))
      (node (ref "C29") (pin "1") (pinfunction "1_1") (pintype "passive"))
      (node (ref "C30") (pin "2") (pinfunction "2_2") (pintype "passive"))
      (node (ref "R20") (pin "2") (pinfunction "2_2") (pintype "passive"))
      (node (ref "R21") (pin "2") (pinfunction "2_2") (pintype "passive"))
      (node (ref "R24") (pin "2") (pinfunction "2_2") (pintype "passive"))
      (node (ref "R25") (pin "2") (pinfunction "2_2") (pintype "passive"))
      (node (ref "R26") (pin "2") (pinfunction "2_2") (pintype "passive"))
      (node (ref "R31") (pin "1") (pinfunction "1_1") (pintype "passive"))
      (node (ref "U4") (pin "26") (pinfunction "VDD33_26") (pintype "power_in"))
      (node (ref "U4") (pin "43") (pinfunction "VDD33_43") (pintype "power_in"))
      (node (ref "U4") (pin "53") (pinfunction "VDD33_53") (pintype "power_in"))
      (node (ref "U4") (pin "62") (pinfunction "VDD33_62") (pintype "power_in"))
      (node (ref "U4") (pin "67") (pinfunction "VDD33_67") (pintype "power_in"))
      (node (ref "U4") (pin "79") (pinfunction "VDD33_79") (pintype "power_in"))
      (node (ref "U4") (pin "88") (pinfunction "VDD33_88") (pintype "power_in"))
      (node (ref "U4") (pin "99") (pinfunction "VDD33_99") (pintype "power_in"))
      (node (ref "U5") (pin "8") (pinfunction "VCC_8") (pintype "power_in"))
      (node (ref "Y1") (pin "1") (pinfunction "~{STANDBY}_1") (pintype "input"))
      (node (ref "Y1") (pin "4") (pinfunction "VDD_4") (pintype "power_in"))
    )
    (net (code "87") (name "unconnected-(U4A-ATEST-Pad96)") (class "Default")
      (node (ref "U4") (pin "96") (pinfunction "ATEST_96") (pintype "passive+no_connect"))
    )
    (net (code "88") (name "unconnected-(U4A-NC-Pad4)") (class "Default")
      (node (ref "U4") (pin "4") (pinfunction "NC_4") (pintype "passive+no_connect"))
    )
    (net (code "89") (name "unconnected-(U4A-NC-Pad12)") (class "Default")
      (node (ref "U4") (pin "12") (pinfunction "NC_12") (pintype "passive+no_connect"))
    )
    (net (code "90") (name "unconnected-(U4A-NC-Pad13)") (class "Default")
      (node (ref "U4") (pin "13") (pinfunction "NC_13") (pintype "passive+no_connect"))
    )
    (net (code "91") (name "unconnected-(U4A-NC-Pad80)") (class "Default")
      (node (ref "U4") (pin "80") (pinfunction "NC_80") (pintype "passive+no_connect"))
    )
    (net (code "92") (name "unconnected-(U4A-XTALO-Pad97)") (class "Default")
      (node (ref "U4") (pin "97") (pinfunction "XTALO_97") (pintype "output+no_connect"))
    )
    (net (code "93") (name "unconnected-(U4B-PF8-Pad49)") (class "Default")
      (node (ref "U4") (pin "49") (pinfunction "PF8_49") (pintype "bidirectional+no_connect"))
    )
    (net (code "94") (name "unconnected-(U4B-PF9-Pad50)") (class "Default")
      (node (ref "U4") (pin "50") (pinfunction "PF9_50") (pintype "bidirectional+no_connect"))
    )
    (net (code "95") (name "unconnected-(U4B-PF10-Pad51)") (class "Default")
      (node (ref "U4") (pin "51") (pinfunction "PF10_51") (pintype "bidirectional+no_connect"))
    )
    (net (code "96") (name "unconnected-(U4B-PF11-Pad52)") (class "Default")
      (node (ref "U4") (pin "52") (pinfunction "PF11_52") (pintype "bidirectional+no_connect"))
    )
    (net (code "97") (name "unconnected-(U4B-PF12-Pad54)") (class "Default")
      (node (ref "U4") (pin "54") (pinfunction "PF12_54") (pintype "bidirectional+no_connect"))
    )
    (net (code "98") (name "unconnected-(U4B-PF29-Pad74)") (class "Default")
      (node (ref "U4") (pin "74") (pinfunction "PF29_74") (pintype "bidirectional"))
    )
  )
)
